# uController.net
KiCad netlist of a schematic drawn in Altium Designer
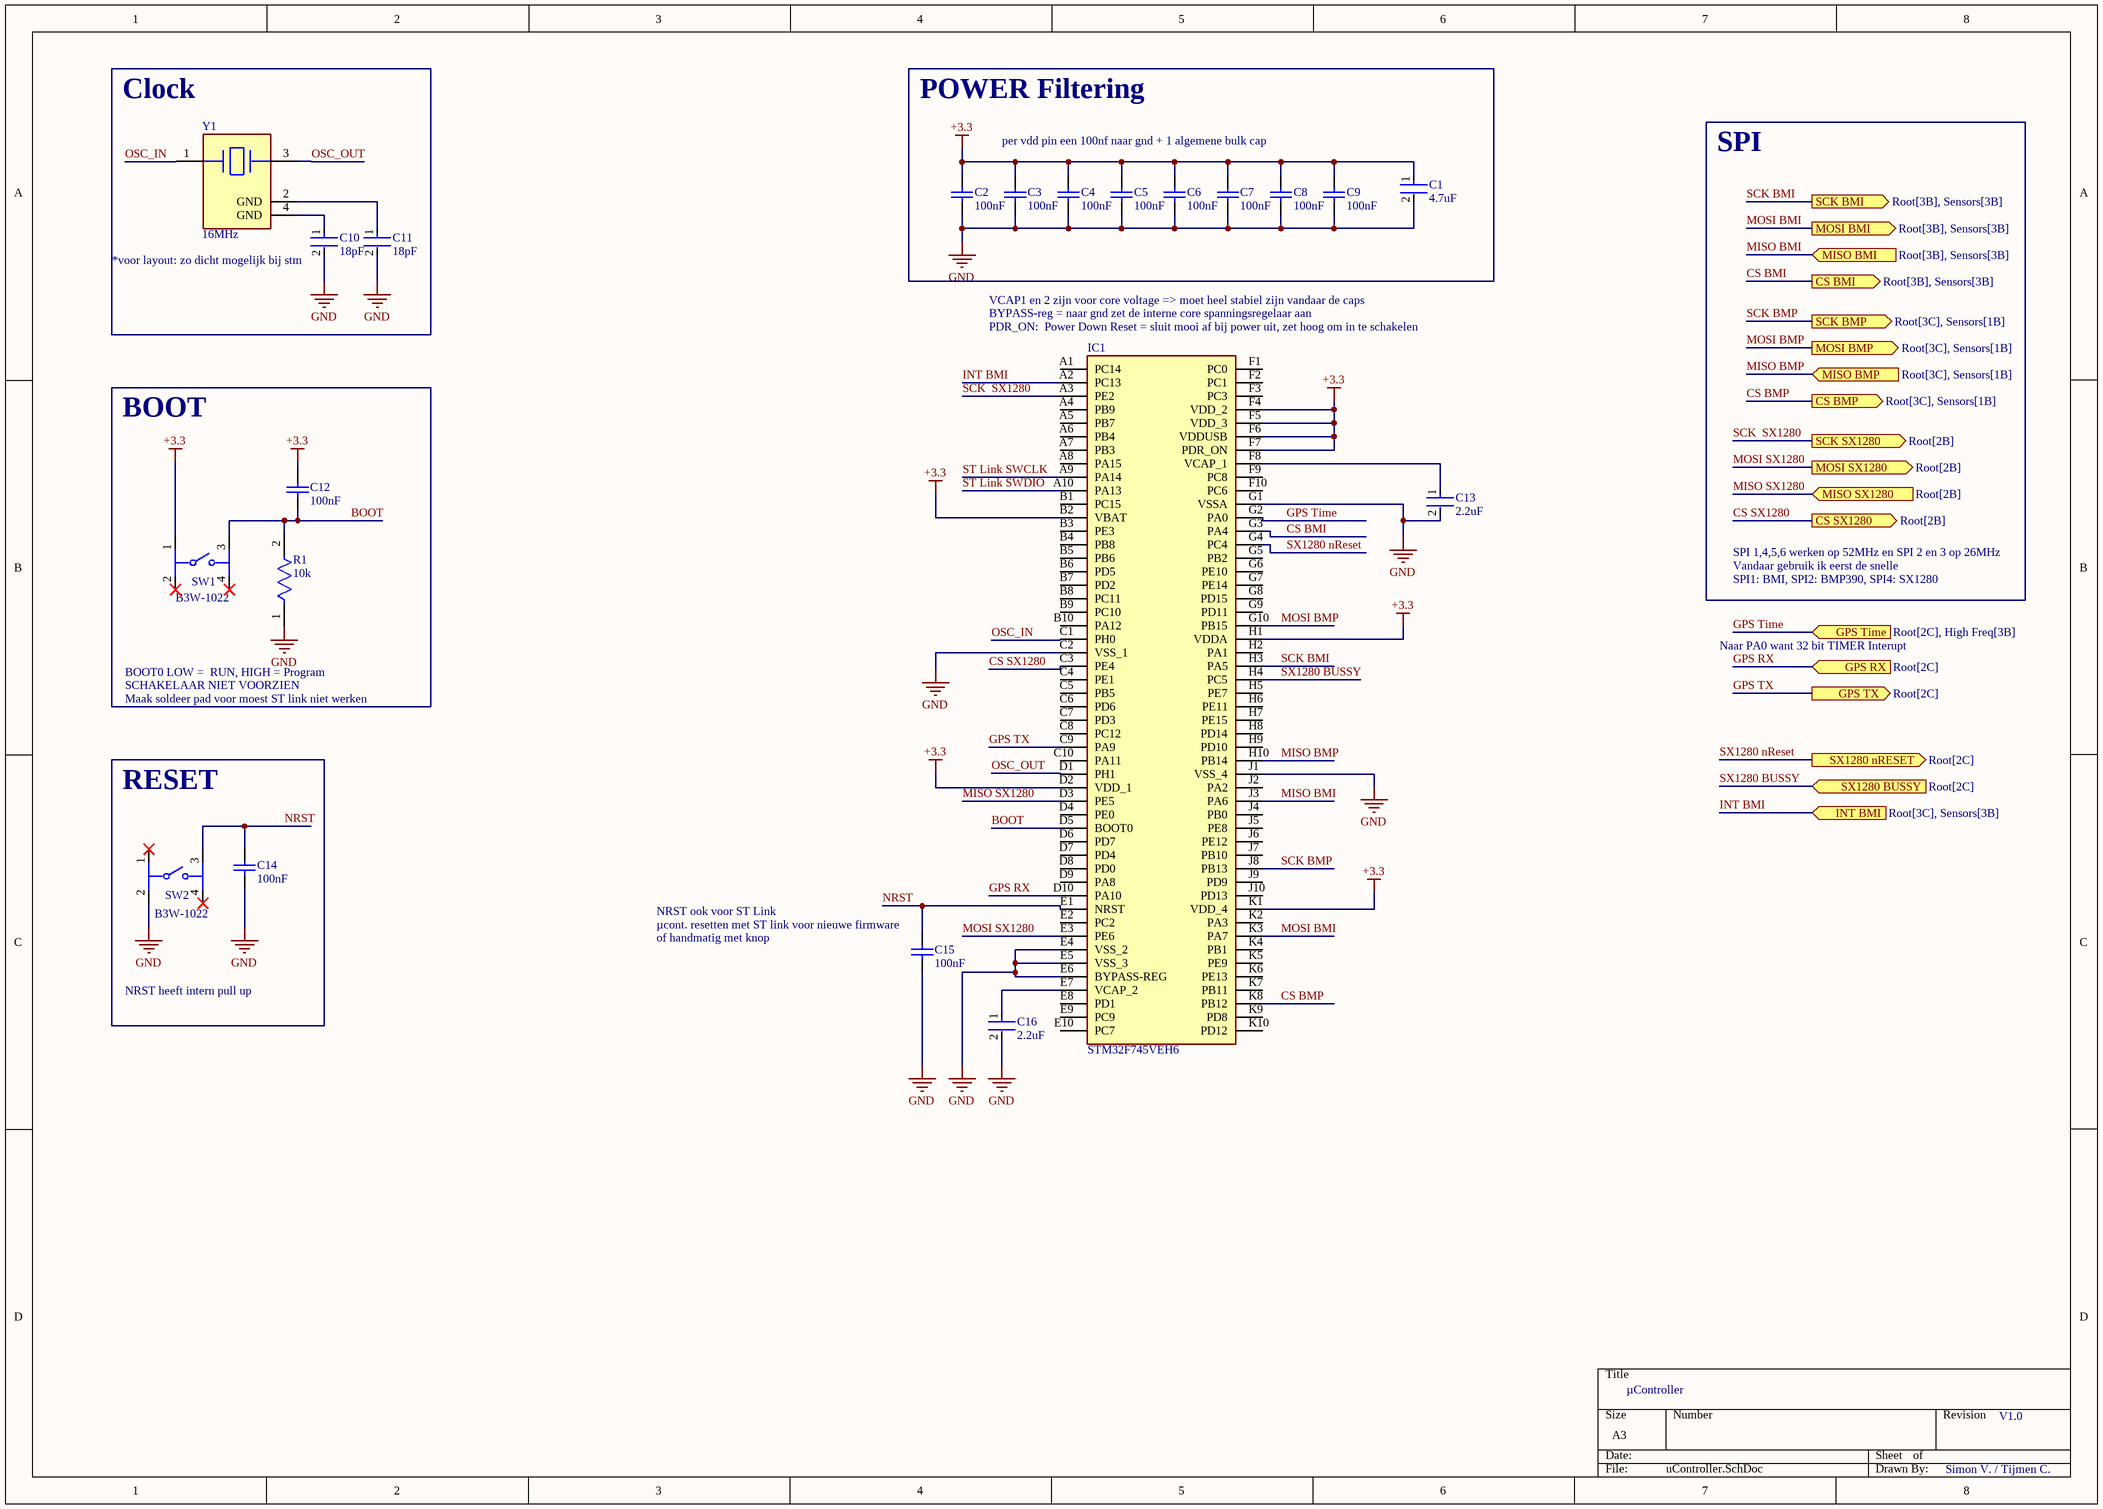
[diagram p0: uController.SchDoc]

(export (version "E")
  (design (tool "Eeschema 10.0.6"))
  (components
    (comp (ref "C1")
      (value "4.7uF")
      (footprint "FP-CC0603-DC-MFG")
      (description "CAP CER 4.7UF 6.3V X7R 0603")
      (fields (field (name "TOLERANCE") "20%"))
      (libsource (lib "Altium Content Vault") (part "11868f565c42a9108669ba33697ecf6"))
    )
    (comp (ref "C2")
      (value "100nF")
      (footprint "CAPC1608X92X38ML15T08")
      (fields (field (name "PART NUMBER") "VJ0603Y104MXXAC") (field (name "MANUFACTURER") "Vitramon"))
      (libsource (lib "Altium Content Vault") (part "CAP"))
    )
    (comp (ref "C3")
      (value "100nF")
      (footprint "CAPC1608X92X38ML15T08")
      (fields (field (name "PART NUMBER") "VJ0603Y104MXXAC") (field (name "MANUFACTURER") "Vitramon"))
      (libsource (lib "Altium Content Vault") (part "CAP"))
    )
    (comp (ref "C4")
      (value "100nF")
      (footprint "CAPC1608X92X38ML15T08")
      (fields (field (name "PART NUMBER") "VJ0603Y104MXXAC") (field (name "MANUFACTURER") "Vitramon"))
      (libsource (lib "Altium Content Vault") (part "CAP"))
    )
    (comp (ref "C5")
      (value "100nF")
      (footprint "CAPC1608X92X38ML15T08")
      (fields (field (name "PART NUMBER") "VJ0603Y104MXXAC") (field (name "MANUFACTURER") "Vitramon"))
      (libsource (lib "Altium Content Vault") (part "CAP"))
    )
    (comp (ref "C6")
      (value "100nF")
      (footprint "CAPC1608X92X38ML15T08")
      (fields (field (name "PART NUMBER") "VJ0603Y104MXXAC") (field (name "MANUFACTURER") "Vitramon"))
      (libsource (lib "Altium Content Vault") (part "CAP"))
    )
    (comp (ref "C7")
      (value "100nF")
      (footprint "CAPC1608X92X38ML15T08")
      (fields (field (name "PART NUMBER") "VJ0603Y104MXXAC") (field (name "MANUFACTURER") "Vitramon"))
      (libsource (lib "Altium Content Vault") (part "CAP"))
    )
    (comp (ref "C8")
      (value "100nF")
      (footprint "CAPC1608X92X38ML15T08")
      (fields (field (name "PART NUMBER") "VJ0603Y104MXXAC") (field (name "MANUFACTURER") "Vitramon"))
      (libsource (lib "Altium Content Vault") (part "CAP"))
    )
    (comp (ref "C9")
      (value "100nF")
      (footprint "CAPC1608X92X38ML15T08")
      (fields (field (name "PART NUMBER") "VJ0603Y104MXXAC") (field (name "MANUFACTURER") "Vitramon"))
      (libsource (lib "Altium Content Vault") (part "CAP"))
    )
    (comp (ref "C10")
      (value "18pF")
      (footprint "FP-C0603C-CF-MFG")
      (description "C0603 18 pF C0G 30ppm/°C 1.00% 50 V")
      (fields
        (field (name "MANUFACTURER") "KEMET")
        (field (name "MANUFACTURER PART NUMBER") "C0603C180F5GACAUTO")
      )
      (libsource (lib "Altium Content Vault") (part "b4654b650e69147ec39a6b967a45e02"))
    )
    (comp (ref "C11")
      (value "18pF")
      (footprint "FP-C0603C-CF-MFG")
      (description "C0603 18 pF C0G 30ppm/°C 1.00% 50 V")
      (fields
        (field (name "MANUFACTURER") "KEMET")
        (field (name "MANUFACTURER PART NUMBER") "C0603C180F5GACAUTO")
      )
      (libsource (lib "Altium Content Vault") (part "b4654b650e69147ec39a6b967a45e02"))
    )
    (comp (ref "C12")
      (value "100nF")
      (footprint "CAPC1608X92X38ML15T08")
      (fields (field (name "PART NUMBER") "VJ0603Y104MXXAC") (field (name "MANUFACTURER") "Vitramon"))
      (libsource (lib "Altium Content Vault") (part "CAP"))
    )
    (comp (ref "C13")
      (value "2.2uF")
      (footprint "FP-CC0603-DA-MFG")
      (description "CC0603 2.2 uF X5R 10.00% 16 V")
      (fields
        (field (name "MANUFACTURER") "YAGEO")
        (field (name "MANUFACTURER PART NUMBER") "CC0603KPX5R7BB225")
      )
      (libsource (lib "Altium Content Vault") (part "11868f565c42a9108669ba33697ecf6"))
    )
    (comp (ref "C14")
      (value "100nF")
      (footprint "CAPC1608X92X38ML15T08")
      (fields (field (name "PART NUMBER") "VJ0603Y104MXXAC") (field (name "MANUFACTURER") "Vitramon"))
      (libsource (lib "Altium Content Vault") (part "CAP"))
    )
    (comp (ref "C15")
      (value "100nF")
      (footprint "CAPC1608X92X38ML15T08")
      (fields (field (name "PART NUMBER") "VJ0603Y104MXXAC") (field (name "MANUFACTURER") "Vitramon"))
      (libsource (lib "Altium Content Vault") (part "CAP"))
    )
    (comp (ref "C16")
      (value "2.2uF")
      (footprint "FP-CC0603-DA-MFG")
      (description "CC0603 2.2 uF X5R 10.00% 16 V")
      (fields
        (field (name "MANUFACTURER") "YAGEO")
        (field (name "MANUFACTURER PART NUMBER") "CC0603KPX5R7BB225")
      )
      (libsource (lib "Altium Content Vault") (part "11868f565c42a9108669ba33697ecf6"))
    )
    (comp (ref "IC1")
      (value "STM32F745VEH6")
      (footprint "SamacSys:BGA100C80P10X10_800X800X110")
      (description "Integrated Circuit")
      (fields (field (name "MOUSER PART NUMBER") "511-STM32F745VEH6"))
      (libsource (lib "*") (part "STM32F745VEH6"))
    )
    (comp (ref "R1")
      (value "10k")
      (footprint "FP-MCT0603-MFG")
      (description "RES SMD 100 OHM 1% 1/8W 0603")
      (fields (field (name "TOLERANCE") "0.1%"))
      (libsource (lib "Altium Content Vault") (part "1029c3af85768c4190bb7ad29bc67b5"))
    )
    (comp (ref "SW1")
      (value "B3W-1022")
      (footprint "FP-B3W-1022-MFG")
      (description "SWITCH TACTILE SPST-NO 0.05A 24V")
      (libsource (lib "Altium Content Vault") (part "b8895f3f4cefb76e1819d2863dba89b"))
    )
    (comp (ref "SW2")
      (value "B3W-1022")
      (footprint "FP-B3W-1022-MFG")
      (description "SWITCH TACTILE SPST-NO 0.05A 24V")
      (libsource (lib "Altium Content Vault") (part "b8895f3f4cefb76e1819d2863dba89b"))
    )
    (comp (ref "Y1")
      (value "16MHz")
      (footprint "FP-ABM8-MFG")
      (description "Crystal 16MHz ±20ppm 18pF SMD-4 3.2mm x 2.5mm                      ABM8-16.000MHZ-B2-T3")
      (libsource (lib "Altium Content Vault") (part "dfdb7f9a12507849fb681da9a70121c"))
    )
  )
  (nets
    (net (code "1") (name "+3.3") (class "Default")
      (node (ref "C1") (pin "1") (pinfunction "1_1") (pintype "passive"))
      (node (ref "C12") (pin "2") (pinfunction "2_2") (pintype "passive"))
      (node (ref "C2") (pin "2") (pinfunction "2_2") (pintype "passive"))
      (node (ref "C3") (pin "2") (pinfunction "2_2") (pintype "passive"))
      (node (ref "C4") (pin "2") (pinfunction "2_2") (pintype "passive"))
      (node (ref "C5") (pin "2") (pinfunction "2_2") (pintype "passive"))
      (node (ref "C6") (pin "2") (pinfunction "2_2") (pintype "passive"))
      (node (ref "C7") (pin "2") (pinfunction "2_2") (pintype "passive"))
      (node (ref "C8") (pin "2") (pinfunction "2_2") (pintype "passive"))
      (node (ref "C9") (pin "2") (pinfunction "2_2") (pintype "passive"))
      (node (ref "IC1") (pin "B2") (pinfunction "VBAT_B2") (pintype "passive"))
      (node (ref "IC1") (pin "D2") (pinfunction "VDD_1_D2") (pintype "passive"))
      (node (ref "IC1") (pin "F4") (pinfunction "VDD_2_F4") (pintype "passive"))
      (node (ref "IC1") (pin "F5") (pinfunction "VDD_3_F5") (pintype "passive"))
      (node (ref "IC1") (pin "F6") (pinfunction "VDDUSB_F6") (pintype "passive"))
      (node (ref "IC1") (pin "F7") (pinfunction "PDR_ON_F7") (pintype "passive"))
      (node (ref "IC1") (pin "H1") (pinfunction "VDDA_H1") (pintype "passive"))
      (node (ref "IC1") (pin "K1") (pinfunction "VDD_4_K1") (pintype "passive"))
      (node (ref "SW1") (pin "1") (pinfunction "1_1") (pintype "passive"))
    )
    (net (code "2") (name "/BOOT") (class "Default")
      (node (ref "C12") (pin "1") (pinfunction "1_1") (pintype "passive"))
      (node (ref "IC1") (pin "D5") (pinfunction "BOOT0_D5") (pintype "passive"))
      (node (ref "R1") (pin "2") (pinfunction "2_2") (pintype "passive"))
      (node (ref "SW1") (pin "3") (pinfunction "3_3") (pintype "passive"))
    )
    (net (code "3") (name "/CS BMI") (class "Default")
      (node (ref "IC1") (pin "G3") (pinfunction "PA4_G3") (pintype "passive"))
    )
    (net (code "4") (name "/CS BMP") (class "Default")
      (node (ref "IC1") (pin "K8") (pinfunction "PB12_K8") (pintype "passive"))
    )
    (net (code "5") (name "/CS SX1280") (class "Default")
      (node (ref "IC1") (pin "C3") (pinfunction "PE4_C3") (pintype "passive"))
    )
    (net (code "6") (name "/GPS RX") (class "Default")
      (node (ref "IC1") (pin "D10") (pinfunction "PA10_D10") (pintype "passive"))
    )
    (net (code "7") (name "/GPS TX") (class "Default")
      (node (ref "IC1") (pin "C9") (pinfunction "PA9_C9") (pintype "passive"))
    )
    (net (code "8") (name "/GPS Time") (class "Default")
      (node (ref "IC1") (pin "G2") (pinfunction "PA0_G2") (pintype "passive"))
    )
    (net (code "9") (name "/INT BMI") (class "Default")
      (node (ref "IC1") (pin "A2") (pinfunction "PC13_A2") (pintype "passive"))
    )
    (net (code "10") (name "/MISO BMI") (class "Default")
      (node (ref "IC1") (pin "J3") (pinfunction "PA6_J3") (pintype "passive"))
    )
    (net (code "11") (name "/MISO BMP") (class "Default")
      (node (ref "IC1") (pin "H10") (pinfunction "PB14_H10") (pintype "passive"))
    )
    (net (code "12") (name "/MISO SX1280") (class "Default")
      (node (ref "IC1") (pin "D3") (pinfunction "PE5_D3") (pintype "passive"))
    )
    (net (code "13") (name "/MOSI BMI") (class "Default")
      (node (ref "IC1") (pin "K3") (pinfunction "PA7_K3") (pintype "passive"))
    )
    (net (code "14") (name "/MOSI BMP") (class "Default")
      (node (ref "IC1") (pin "G10") (pinfunction "PB15_G10") (pintype "passive"))
    )
    (net (code "15") (name "/MOSI SX1280") (class "Default")
      (node (ref "IC1") (pin "E3") (pinfunction "PE6_E3") (pintype "passive"))
    )
    (net (code "16") (name "/NRST") (class "Default")
      (node (ref "C14") (pin "2") (pinfunction "2_2") (pintype "passive"))
      (node (ref "C15") (pin "2") (pinfunction "2_2") (pintype "passive"))
      (node (ref "IC1") (pin "E1") (pinfunction "NRST_E1") (pintype "passive"))
      (node (ref "SW2") (pin "3") (pinfunction "3_3") (pintype "passive"))
    )
    (net (code "17") (name "/OSC_IN") (class "Default")
      (node (ref "IC1") (pin "C1") (pinfunction "PH0_C1") (pintype "passive"))
      (node (ref "Y1") (pin "1") (pinfunction "1_1") (pintype "passive"))
    )
    (net (code "18") (name "/OSC_OUT") (class "Default")
      (node (ref "IC1") (pin "D1") (pinfunction "PH1_D1") (pintype "passive"))
      (node (ref "Y1") (pin "3") (pinfunction "3_3") (pintype "passive"))
    )
    (net (code "19") (name "/SCK  SX1280") (class "Default")
      (node (ref "IC1") (pin "A3") (pinfunction "PE2_A3") (pintype "passive"))
    )
    (net (code "20") (name "/SCK BMI") (class "Default")
      (node (ref "IC1") (pin "H3") (pinfunction "PA5_H3") (pintype "passive"))
    )
    (net (code "21") (name "/SCK BMP") (class "Default")
      (node (ref "IC1") (pin "J8") (pinfunction "PB13_J8") (pintype "passive"))
    )
    (net (code "22") (name "/ST Link SWCLK") (class "Default")
      (node (ref "IC1") (pin "A9") (pinfunction "PA14_A9") (pintype "passive"))
    )
    (net (code "23") (name "/ST Link SWDIO") (class "Default")
      (node (ref "IC1") (pin "A10") (pinfunction "PA13_A10") (pintype "passive"))
    )
    (net (code "24") (name "/SX1280 BUSSY") (class "Default")
      (node (ref "IC1") (pin "H4") (pinfunction "PC5_H4") (pintype "passive"))
    )
    (net (code "25") (name "/SX1280 nReset") (class "Default")
      (node (ref "IC1") (pin "G4") (pinfunction "PC4_G4") (pintype "passive"))
    )
    (net (code "26") (name "GND") (class "Default")
      (node (ref "C1") (pin "2") (pinfunction "2_2") (pintype "passive"))
      (node (ref "C10") (pin "2") (pinfunction "2_2") (pintype "passive"))
      (node (ref "C11") (pin "2") (pinfunction "2_2") (pintype "passive"))
      (node (ref "C13") (pin "2") (pinfunction "2_2") (pintype "passive"))
      (node (ref "C14") (pin "1") (pinfunction "1_1") (pintype "passive"))
      (node (ref "C15") (pin "1") (pinfunction "1_1") (pintype "passive"))
      (node (ref "C16") (pin "2") (pinfunction "2_2") (pintype "passive"))
      (node (ref "C2") (pin "1") (pinfunction "1_1") (pintype "passive"))
      (node (ref "C3") (pin "1") (pinfunction "1_1") (pintype "passive"))
      (node (ref "C4") (pin "1") (pinfunction "1_1") (pintype "passive"))
      (node (ref "C5") (pin "1") (pinfunction "1_1") (pintype "passive"))
      (node (ref "C6") (pin "1") (pinfunction "1_1") (pintype "passive"))
      (node (ref "C7") (pin "1") (pinfunction "1_1") (pintype "passive"))
      (node (ref "C8") (pin "1") (pinfunction "1_1") (pintype "passive"))
      (node (ref "C9") (pin "1") (pinfunction "1_1") (pintype "passive"))
      (node (ref "IC1") (pin "C2") (pinfunction "VSS_1_C2") (pintype "passive"))
      (node (ref "IC1") (pin "E4") (pinfunction "VSS_2_E4") (pintype "passive"))
      (node (ref "IC1") (pin "E5") (pinfunction "VSS_3_E5") (pintype "passive"))
      (node (ref "IC1") (pin "E6") (pinfunction "BYPASS-REG_E6") (pintype "passive"))
      (node (ref "IC1") (pin "G1") (pinfunction "VSSA_G1") (pintype "passive"))
      (node (ref "IC1") (pin "J1") (pinfunction "VSS_4_J1") (pintype "passive"))
      (node (ref "R1") (pin "1") (pinfunction "1_1") (pintype "passive"))
      (node (ref "SW2") (pin "2") (pinfunction "2_2") (pintype "passive"))
    )
    (net (code "27") (name "Net-(C10-Pad1)") (class "Default")
      (node (ref "C10") (pin "1") (pinfunction "1_1") (pintype "passive"))
      (node (ref "Y1") (pin "4") (pinfunction "GND_4") (pintype "power_in"))
    )
    (net (code "28") (name "Net-(C11-Pad1)") (class "Default")
      (node (ref "C11") (pin "1") (pinfunction "1_1") (pintype "passive"))
      (node (ref "Y1") (pin "2") (pinfunction "GND_2") (pintype "power_in"))
    )
    (net (code "29") (name "Net-(IC1-VCAP_1)") (class "Default")
      (node (ref "C13") (pin "1") (pinfunction "1_1") (pintype "passive"))
      (node (ref "IC1") (pin "F8") (pinfunction "VCAP_1_F8") (pintype "passive"))
    )
    (net (code "30") (name "Net-(IC1-VCAP_2)") (class "Default")
      (node (ref "C16") (pin "1") (pinfunction "1_1") (pintype "passive"))
      (node (ref "IC1") (pin "E7") (pinfunction "VCAP_2_E7") (pintype "passive"))
    )
    (net (code "31") (name "unconnected-(IC1-PA1-PadH2)") (class "Default")
      (node (ref "IC1") (pin "H2") (pinfunction "PA1_H2") (pintype "passive"))
    )
    (net (code "32") (name "unconnected-(IC1-PA2-PadJ2)") (class "Default")
      (node (ref "IC1") (pin "J2") (pinfunction "PA2_J2") (pintype "passive"))
    )
    (net (code "33") (name "unconnected-(IC1-PA3-PadK2)") (class "Default")
      (node (ref "IC1") (pin "K2") (pinfunction "PA3_K2") (pintype "passive"))
    )
    (net (code "34") (name "unconnected-(IC1-PA8-PadD9)") (class "Default")
      (node (ref "IC1") (pin "D9") (pinfunction "PA8_D9") (pintype "passive"))
    )
    (net (code "35") (name "unconnected-(IC1-PA11-PadC10)") (class "Default")
      (node (ref "IC1") (pin "C10") (pinfunction "PA11_C10") (pintype "passive"))
    )
    (net (code "36") (name "unconnected-(IC1-PA12-PadB10)") (class "Default")
      (node (ref "IC1") (pin "B10") (pinfunction "PA12_B10") (pintype "passive"))
    )
    (net (code "37") (name "unconnected-(IC1-PA15-PadA8)") (class "Default")
      (node (ref "IC1") (pin "A8") (pinfunction "PA15_A8") (pintype "passive"))
    )
    (net (code "38") (name "unconnected-(IC1-PB0-PadJ4)") (class "Default")
      (node (ref "IC1") (pin "J4") (pinfunction "PB0_J4") (pintype "passive"))
    )
    (net (code "39") (name "unconnected-(IC1-PB1-PadK4)") (class "Default")
      (node (ref "IC1") (pin "K4") (pinfunction "PB1_K4") (pintype "passive"))
    )
    (net (code "40") (name "unconnected-(IC1-PB2-PadG5)") (class "Default")
      (node (ref "IC1") (pin "G5") (pinfunction "PB2_G5") (pintype "passive"))
    )
    (net (code "41") (name "unconnected-(IC1-PB3-PadA7)") (class "Default")
      (node (ref "IC1") (pin "A7") (pinfunction "PB3_A7") (pintype "passive"))
    )
    (net (code "42") (name "unconnected-(IC1-PB4-PadA6)") (class "Default")
      (node (ref "IC1") (pin "A6") (pinfunction "PB4_A6") (pintype "passive"))
    )
    (net (code "43") (name "unconnected-(IC1-PB5-PadC5)") (class "Default")
      (node (ref "IC1") (pin "C5") (pinfunction "PB5_C5") (pintype "passive"))
    )
    (net (code "44") (name "unconnected-(IC1-PB6-PadB5)") (class "Default")
      (node (ref "IC1") (pin "B5") (pinfunction "PB6_B5") (pintype "passive"))
    )
    (net (code "45") (name "unconnected-(IC1-PB7-PadA5)") (class "Default")
      (node (ref "IC1") (pin "A5") (pinfunction "PB7_A5") (pintype "passive"))
    )
    (net (code "46") (name "unconnected-(IC1-PB8-PadB4)") (class "Default")
      (node (ref "IC1") (pin "B4") (pinfunction "PB8_B4") (pintype "passive"))
    )
    (net (code "47") (name "unconnected-(IC1-PB9-PadA4)") (class "Default")
      (node (ref "IC1") (pin "A4") (pinfunction "PB9_A4") (pintype "passive"))
    )
    (net (code "48") (name "unconnected-(IC1-PB10-PadJ7)") (class "Default")
      (node (ref "IC1") (pin "J7") (pinfunction "PB10_J7") (pintype "passive"))
    )
    (net (code "49") (name "unconnected-(IC1-PB11-PadK7)") (class "Default")
      (node (ref "IC1") (pin "K7") (pinfunction "PB11_K7") (pintype "passive"))
    )
    (net (code "50") (name "unconnected-(IC1-PC0-PadF1)") (class "Default")
      (node (ref "IC1") (pin "F1") (pinfunction "PC0_F1") (pintype "passive"))
    )
    (net (code "51") (name "unconnected-(IC1-PC1-PadF2)") (class "Default")
      (node (ref "IC1") (pin "F2") (pinfunction "PC1_F2") (pintype "passive"))
    )
    (net (code "52") (name "unconnected-(IC1-PC2-PadE2)") (class "Default")
      (node (ref "IC1") (pin "E2") (pinfunction "PC2_E2") (pintype "passive"))
    )
    (net (code "53") (name "unconnected-(IC1-PC3-PadF3)") (class "Default")
      (node (ref "IC1") (pin "F3") (pinfunction "PC3_F3") (pintype "passive"))
    )
    (net (code "54") (name "unconnected-(IC1-PC6-PadF10)") (class "Default")
      (node (ref "IC1") (pin "F10") (pinfunction "PC6_F10") (pintype "passive"))
    )
    (net (code "55") (name "unconnected-(IC1-PC7-PadE10)") (class "Default")
      (node (ref "IC1") (pin "E10") (pinfunction "PC7_E10") (pintype "passive"))
    )
    (net (code "56") (name "unconnected-(IC1-PC8-PadF9)") (class "Default")
      (node (ref "IC1") (pin "F9") (pinfunction "PC8_F9") (pintype "passive"))
    )
    (net (code "57") (name "unconnected-(IC1-PC9-PadE9)") (class "Default")
      (node (ref "IC1") (pin "E9") (pinfunction "PC9_E9") (pintype "passive"))
    )
    (net (code "58") (name "unconnected-(IC1-PC10-PadB9)") (class "Default")
      (node (ref "IC1") (pin "B9") (pinfunction "PC10_B9") (pintype "passive"))
    )
    (net (code "59") (name "unconnected-(IC1-PC11-PadB8)") (class "Default")
      (node (ref "IC1") (pin "B8") (pinfunction "PC11_B8") (pintype "passive"))
    )
    (net (code "60") (name "unconnected-(IC1-PC12-PadC8)") (class "Default")
      (node (ref "IC1") (pin "C8") (pinfunction "PC12_C8") (pintype "passive"))
    )
    (net (code "61") (name "unconnected-(IC1-PC14-PadA1)") (class "Default")
      (node (ref "IC1") (pin "A1") (pinfunction "PC14_A1") (pintype "passive"))
    )
    (net (code "62") (name "unconnected-(IC1-PC15-PadB1)") (class "Default")
      (node (ref "IC1") (pin "B1") (pinfunction "PC15_B1") (pintype "passive"))
    )
    (net (code "63") (name "unconnected-(IC1-PD0-PadD8)") (class "Default")
      (node (ref "IC1") (pin "D8") (pinfunction "PD0_D8") (pintype "passive"))
    )
    (net (code "64") (name "unconnected-(IC1-PD1-PadE8)") (class "Default")
      (node (ref "IC1") (pin "E8") (pinfunction "PD1_E8") (pintype "passive"))
    )
    (net (code "65") (name "unconnected-(IC1-PD2-PadB7)") (class "Default")
      (node (ref "IC1") (pin "B7") (pinfunction "PD2_B7") (pintype "passive"))
    )
    (net (code "66") (name "unconnected-(IC1-PD3-PadC7)") (class "Default")
      (node (ref "IC1") (pin "C7") (pinfunction "PD3_C7") (pintype "passive"))
    )
    (net (code "67") (name "unconnected-(IC1-PD4-PadD7)") (class "Default")
      (node (ref "IC1") (pin "D7") (pinfunction "PD4_D7") (pintype "passive"))
    )
    (net (code "68") (name "unconnected-(IC1-PD5-PadB6)") (class "Default")
      (node (ref "IC1") (pin "B6") (pinfunction "PD5_B6") (pintype "passive"))
    )
    (net (code "69") (name "unconnected-(IC1-PD6-PadC6)") (class "Default")
      (node (ref "IC1") (pin "C6") (pinfunction "PD6_C6") (pintype "passive"))
    )
    (net (code "70") (name "unconnected-(IC1-PD7-PadD6)") (class "Default")
      (node (ref "IC1") (pin "D6") (pinfunction "PD7_D6") (pintype "passive"))
    )
    (net (code "71") (name "unconnected-(IC1-PD8-PadK9)") (class "Default")
      (node (ref "IC1") (pin "K9") (pinfunction "PD8_K9") (pintype "passive"))
    )
    (net (code "72") (name "unconnected-(IC1-PD9-PadJ9)") (class "Default")
      (node (ref "IC1") (pin "J9") (pinfunction "PD9_J9") (pintype "passive"))
    )
    (net (code "73") (name "unconnected-(IC1-PD10-PadH9)") (class "Default")
      (node (ref "IC1") (pin "H9") (pinfunction "PD10_H9") (pintype "passive"))
    )
    (net (code "74") (name "unconnected-(IC1-PD11-PadG9)") (class "Default")
      (node (ref "IC1") (pin "G9") (pinfunction "PD11_G9") (pintype "passive"))
    )
    (net (code "75") (name "unconnected-(IC1-PD12-PadK10)") (class "Default")
      (node (ref "IC1") (pin "K10") (pinfunction "PD12_K10") (pintype "passive"))
    )
    (net (code "76") (name "unconnected-(IC1-PD13-PadJ10)") (class "Default")
      (node (ref "IC1") (pin "J10") (pinfunction "PD13_J10") (pintype "passive"))
    )
    (net (code "77") (name "unconnected-(IC1-PD14-PadH8)") (class "Default")
      (node (ref "IC1") (pin "H8") (pinfunction "PD14_H8") (pintype "passive"))
    )
    (net (code "78") (name "unconnected-(IC1-PD15-PadG8)") (class "Default")
      (node (ref "IC1") (pin "G8") (pinfunction "PD15_G8") (pintype "passive"))
    )
    (net (code "79") (name "unconnected-(IC1-PE0-PadD4)") (class "Default")
      (node (ref "IC1") (pin "D4") (pinfunction "PE0_D4") (pintype "passive"))
    )
    (net (code "80") (name "unconnected-(IC1-PE1-PadC4)") (class "Default")
      (node (ref "IC1") (pin "C4") (pinfunction "PE1_C4") (pintype "passive"))
    )
    (net (code "81") (name "unconnected-(IC1-PE3-PadB3)") (class "Default")
      (node (ref "IC1") (pin "B3") (pinfunction "PE3_B3") (pintype "passive"))
    )
    (net (code "82") (name "unconnected-(IC1-PE7-PadH5)") (class "Default")
      (node (ref "IC1") (pin "H5") (pinfunction "PE7_H5") (pintype "passive"))
    )
    (net (code "83") (name "unconnected-(IC1-PE8-PadJ5)") (class "Default")
      (node (ref "IC1") (pin "J5") (pinfunction "PE8_J5") (pintype "passive"))
    )
    (net (code "84") (name "unconnected-(IC1-PE9-PadK5)") (class "Default")
      (node (ref "IC1") (pin "K5") (pinfunction "PE9_K5") (pintype "passive"))
    )
    (net (code "85") (name "unconnected-(IC1-PE10-PadG6)") (class "Default")
      (node (ref "IC1") (pin "G6") (pinfunction "PE10_G6") (pintype "passive"))
    )
    (net (code "86") (name "unconnected-(IC1-PE11-PadH6)") (class "Default")
      (node (ref "IC1") (pin "H6") (pinfunction "PE11_H6") (pintype "passive"))
    )
    (net (code "87") (name "unconnected-(IC1-PE12-PadJ6)") (class "Default")
      (node (ref "IC1") (pin "J6") (pinfunction "PE12_J6") (pintype "passive"))
    )
    (net (code "88") (name "unconnected-(IC1-PE13-PadK6)") (class "Default")
      (node (ref "IC1") (pin "K6") (pinfunction "PE13_K6") (pintype "passive"))
    )
    (net (code "89") (name "unconnected-(IC1-PE14-PadG7)") (class "Default")
      (node (ref "IC1") (pin "G7") (pinfunction "PE14_G7") (pintype "passive"))
    )
    (net (code "90") (name "unconnected-(IC1-PE15-PadH7)") (class "Default")
      (node (ref "IC1") (pin "H7") (pinfunction "PE15_H7") (pintype "passive"))
    )
    (net (code "91") (name "unconnected-(SW1-Pad2)") (class "Default")
      (node (ref "SW1") (pin "2") (pinfunction "2_2") (pintype "passive+no_connect"))
    )
    (net (code "92") (name "unconnected-(SW1-Pad4)") (class "Default")
      (node (ref "SW1") (pin "4") (pinfunction "4_4") (pintype "passive+no_connect"))
    )
    (net (code "93") (name "unconnected-(SW2-Pad1)") (class "Default")
      (node (ref "SW2") (pin "1") (pinfunction "1_1") (pintype "passive+no_connect"))
    )
    (net (code "94") (name "unconnected-(SW2-Pad4)") (class "Default")
      (node (ref "SW2") (pin "4") (pinfunction "4_4") (pintype "passive+no_connect"))
    )
  )
)
